# board.net
KiCad netlist of a schematic drawn in EAGLE
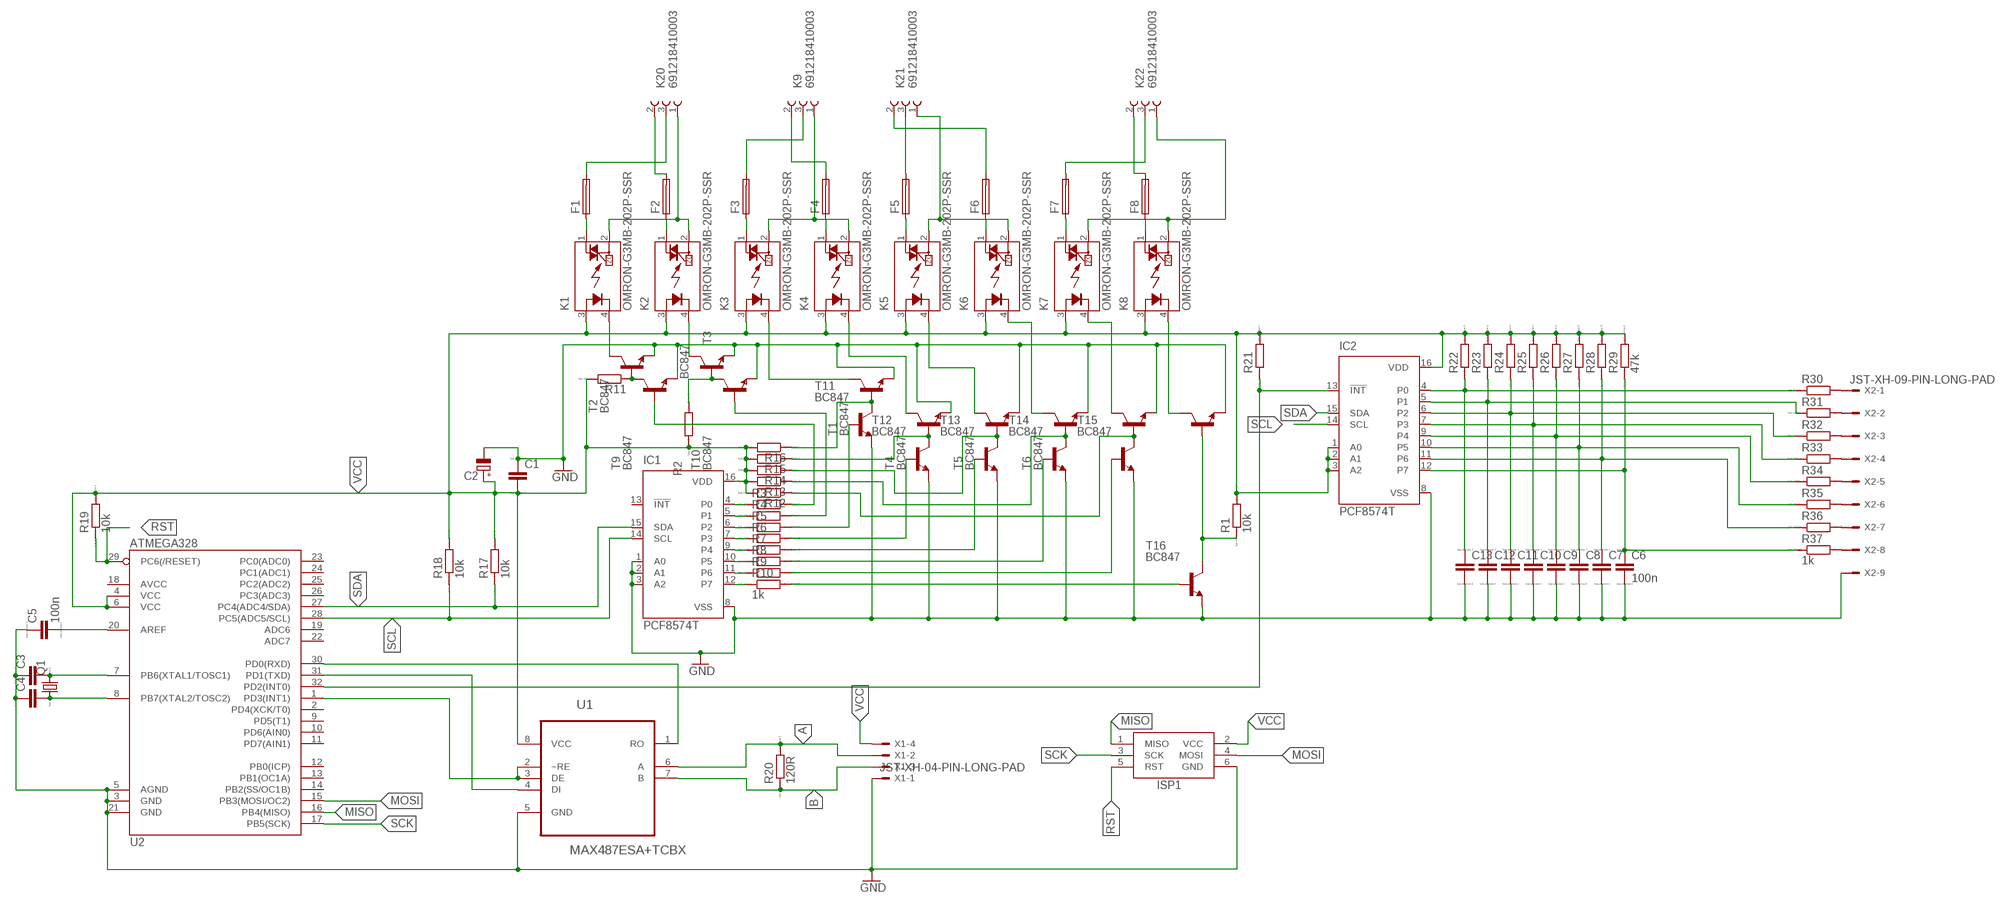
[diagram p0: schematic, sheet 1]

(export (version "E")
  (design (tool "Eeschema 10.0.6"))
  (components
    (comp (ref "C1")
      (value "CC1206")
      (footprint "eagle-import:C1206")
      (libsource (lib "eagle-import") (part "CC1206"))
    )
    (comp (ref "C2")
      (value "CPOL-EU150CLZ-0810")
      (footprint "eagle-import:150CLZ-0810")
      (libsource (lib "eagle-import") (part "CPOL-EU150CLZ-0810"))
    )
    (comp (ref "C3") (value "C") (footprint "eagle-import:C0805") (libsource (lib "eagle-import") (part "C")))
    (comp (ref "C4") (value "C") (footprint "eagle-import:C0805") (libsource (lib "eagle-import") (part "C")))
    (comp (ref "C5")
      (value "100n")
      (footprint "eagle-import:C0805")
      (libsource (lib "eagle-import") (part "C"))
    )
    (comp (ref "C6")
      (value "100n")
      (footprint "eagle-import:C0805")
      (libsource (lib "eagle-import") (part "C"))
    )
    (comp (ref "C7") (value "C") (footprint "eagle-import:C0805") (libsource (lib "eagle-import") (part "C")))
    (comp (ref "C8") (value "C") (footprint "eagle-import:C0805") (libsource (lib "eagle-import") (part "C")))
    (comp (ref "C9") (value "C") (footprint "eagle-import:C0805") (libsource (lib "eagle-import") (part "C")))
    (comp (ref "C10")
      (value "C")
      (footprint "eagle-import:C0805")
      (libsource (lib "eagle-import") (part "C"))
    )
    (comp (ref "C11")
      (value "C")
      (footprint "eagle-import:C0805")
      (libsource (lib "eagle-import") (part "C"))
    )
    (comp (ref "C12")
      (value "C")
      (footprint "eagle-import:C0805")
      (libsource (lib "eagle-import") (part "C"))
    )
    (comp (ref "C13")
      (value "C")
      (footprint "eagle-import:C0805")
      (libsource (lib "eagle-import") (part "C"))
    )
    (comp (ref "F1")
      (value "FUSELITTLEFUSE")
      (footprint "eagle-import:LITTLEFUSE")
      (libsource (lib "eagle-import") (part "FUSELITTLEFUSE"))
    )
    (comp (ref "F2")
      (value "FUSELITTLEFUSE")
      (footprint "eagle-import:LITTLEFUSE")
      (libsource (lib "eagle-import") (part "FUSELITTLEFUSE"))
    )
    (comp (ref "F3")
      (value "FUSELITTLEFUSE")
      (footprint "eagle-import:LITTLEFUSE")
      (libsource (lib "eagle-import") (part "FUSELITTLEFUSE"))
    )
    (comp (ref "F4")
      (value "FUSELITTLEFUSE")
      (footprint "eagle-import:LITTLEFUSE")
      (libsource (lib "eagle-import") (part "FUSELITTLEFUSE"))
    )
    (comp (ref "F5")
      (value "FUSELITTLEFUSE")
      (footprint "eagle-import:LITTLEFUSE")
      (libsource (lib "eagle-import") (part "FUSELITTLEFUSE"))
    )
    (comp (ref "F6")
      (value "FUSELITTLEFUSE")
      (footprint "eagle-import:LITTLEFUSE")
      (libsource (lib "eagle-import") (part "FUSELITTLEFUSE"))
    )
    (comp (ref "F7")
      (value "FUSELITTLEFUSE")
      (footprint "eagle-import:LITTLEFUSE")
      (libsource (lib "eagle-import") (part "FUSELITTLEFUSE"))
    )
    (comp (ref "F8")
      (value "FUSELITTLEFUSE")
      (footprint "eagle-import:LITTLEFUSE")
      (libsource (lib "eagle-import") (part "FUSELITTLEFUSE"))
    )
    (comp (ref "IC1")
      (value "PCF8574T")
      (footprint "eagle-import:SO16W")
      (fields (field (name "MPN") "PCF8574T/3,512"))
      (libsource (lib "eagle-import") (part "PCF8574T"))
    )
    (comp (ref "IC2")
      (value "PCF8574T")
      (footprint "eagle-import:SO16W")
      (fields (field (name "MPN") "PCF8574T/3,512"))
      (libsource (lib "eagle-import") (part "PCF8574T"))
    )
    (comp (ref "ISP1")
      (value "AVRISP-6")
      (footprint "eagle-import:AVRISP")
      (libsource (lib "eagle-import") (part "AVRISP-6"))
    )
    (comp (ref "K1")
      (value "OMRON-G3MB-202P-SSR")
      (footprint "eagle-import:OMRON-G3MB-202P-SSR")
      (libsource (lib "eagle-import") (part "OMRON-G3MB-202P-SSR"))
    )
    (comp (ref "K2")
      (value "OMRON-G3MB-202P-SSR")
      (footprint "eagle-import:OMRON-G3MB-202P-SSR")
      (libsource (lib "eagle-import") (part "OMRON-G3MB-202P-SSR"))
    )
    (comp (ref "K3")
      (value "OMRON-G3MB-202P-SSR")
      (footprint "eagle-import:OMRON-G3MB-202P-SSR")
      (libsource (lib "eagle-import") (part "OMRON-G3MB-202P-SSR"))
    )
    (comp (ref "K4")
      (value "OMRON-G3MB-202P-SSR")
      (footprint "eagle-import:OMRON-G3MB-202P-SSR")
      (libsource (lib "eagle-import") (part "OMRON-G3MB-202P-SSR"))
    )
    (comp (ref "K5")
      (value "OMRON-G3MB-202P-SSR")
      (footprint "eagle-import:OMRON-G3MB-202P-SSR")
      (libsource (lib "eagle-import") (part "OMRON-G3MB-202P-SSR"))
    )
    (comp (ref "K6")
      (value "OMRON-G3MB-202P-SSR")
      (footprint "eagle-import:OMRON-G3MB-202P-SSR")
      (libsource (lib "eagle-import") (part "OMRON-G3MB-202P-SSR"))
    )
    (comp (ref "K7")
      (value "OMRON-G3MB-202P-SSR")
      (footprint "eagle-import:OMRON-G3MB-202P-SSR")
      (libsource (lib "eagle-import") (part "OMRON-G3MB-202P-SSR"))
    )
    (comp (ref "K8")
      (value "OMRON-G3MB-202P-SSR")
      (footprint "eagle-import:OMRON-G3MB-202P-SSR")
      (libsource (lib "eagle-import") (part "OMRON-G3MB-202P-SSR"))
    )
    (comp (ref "K9")
      (value "691218410003")
      (footprint "eagle-import:691218410003")
      (libsource (lib "eagle-import") (part "691218410003"))
    )
    (comp (ref "K20")
      (value "691218410003")
      (footprint "eagle-import:691218410003")
      (libsource (lib "eagle-import") (part "691218410003"))
    )
    (comp (ref "K21")
      (value "691218410003")
      (footprint "eagle-import:691218410003")
      (libsource (lib "eagle-import") (part "691218410003"))
    )
    (comp (ref "K22")
      (value "691218410003")
      (footprint "eagle-import:691218410003")
      (libsource (lib "eagle-import") (part "691218410003"))
    )
    (comp (ref "Q1")
      (value "CRYSTALHC49S")
      (footprint "eagle-import:HC49_S")
      (libsource (lib "eagle-import") (part "CRYSTALHC49S"))
    )
    (comp (ref "R1")
      (value "10k")
      (footprint "eagle-import:R1206")
      (libsource (lib "eagle-import") (part "RR1206"))
    )
    (comp (ref "R2")
      (value "RR1206")
      (footprint "eagle-import:R1206")
      (libsource (lib "eagle-import") (part "RR1206"))
    )
    (comp (ref "R3")
      (value "RR1206")
      (footprint "eagle-import:R1206")
      (libsource (lib "eagle-import") (part "RR1206"))
    )
    (comp (ref "R4")
      (value "RR1206")
      (footprint "eagle-import:R1206")
      (libsource (lib "eagle-import") (part "RR1206"))
    )
    (comp (ref "R5")
      (value "RR1206")
      (footprint "eagle-import:R1206")
      (libsource (lib "eagle-import") (part "RR1206"))
    )
    (comp (ref "R6")
      (value "RR1206")
      (footprint "eagle-import:R1206")
      (libsource (lib "eagle-import") (part "RR1206"))
    )
    (comp (ref "R7")
      (value "RR1206")
      (footprint "eagle-import:R1206")
      (libsource (lib "eagle-import") (part "RR1206"))
    )
    (comp (ref "R8")
      (value "RR1206")
      (footprint "eagle-import:R1206")
      (libsource (lib "eagle-import") (part "RR1206"))
    )
    (comp (ref "R9")
      (value "RR1206")
      (footprint "eagle-import:R1206")
      (libsource (lib "eagle-import") (part "RR1206"))
    )
    (comp (ref "R10")
      (value "1k")
      (footprint "eagle-import:R1206")
      (libsource (lib "eagle-import") (part "RR1206"))
    )
    (comp (ref "R11")
      (value "RR1206")
      (footprint "eagle-import:R1206")
      (libsource (lib "eagle-import") (part "RR1206"))
    )
    (comp (ref "R12")
      (value "RR1206")
      (footprint "eagle-import:R1206")
      (libsource (lib "eagle-import") (part "RR1206"))
    )
    (comp (ref "R13")
      (value "RR1206")
      (footprint "eagle-import:R1206")
      (libsource (lib "eagle-import") (part "RR1206"))
    )
    (comp (ref "R14")
      (value "RR1206")
      (footprint "eagle-import:R1206")
      (libsource (lib "eagle-import") (part "RR1206"))
    )
    (comp (ref "R15")
      (value "RR1206")
      (footprint "eagle-import:R1206")
      (libsource (lib "eagle-import") (part "RR1206"))
    )
    (comp (ref "R16")
      (value "RR1206")
      (footprint "eagle-import:R1206")
      (libsource (lib "eagle-import") (part "RR1206"))
    )
    (comp (ref "R17")
      (value "10k")
      (footprint "eagle-import:R1206")
      (libsource (lib "eagle-import") (part "RR1206"))
    )
    (comp (ref "R18")
      (value "10k")
      (footprint "eagle-import:R1206")
      (libsource (lib "eagle-import") (part "RR1206"))
    )
    (comp (ref "R19")
      (value "10k")
      (footprint "eagle-import:R1206")
      (libsource (lib "eagle-import") (part "RR1206"))
    )
    (comp (ref "R20")
      (value "120R")
      (footprint "eagle-import:R1206")
      (libsource (lib "eagle-import") (part "RR1206"))
    )
    (comp (ref "R21")
      (value "RR1206")
      (footprint "eagle-import:R1206")
      (libsource (lib "eagle-import") (part "RR1206"))
    )
    (comp (ref "R22")
      (value "RR1206")
      (footprint "eagle-import:R1206")
      (libsource (lib "eagle-import") (part "RR1206"))
    )
    (comp (ref "R23")
      (value "RR1206")
      (footprint "eagle-import:R1206")
      (libsource (lib "eagle-import") (part "RR1206"))
    )
    (comp (ref "R24")
      (value "RR1206")
      (footprint "eagle-import:R1206")
      (libsource (lib "eagle-import") (part "RR1206"))
    )
    (comp (ref "R25")
      (value "RR1206")
      (footprint "eagle-import:R1206")
      (libsource (lib "eagle-import") (part "RR1206"))
    )
    (comp (ref "R26")
      (value "RR1206")
      (footprint "eagle-import:R1206")
      (libsource (lib "eagle-import") (part "RR1206"))
    )
    (comp (ref "R27")
      (value "RR1206")
      (footprint "eagle-import:R1206")
      (libsource (lib "eagle-import") (part "RR1206"))
    )
    (comp (ref "R28")
      (value "RR1206")
      (footprint "eagle-import:R1206")
      (libsource (lib "eagle-import") (part "RR1206"))
    )
    (comp (ref "R29")
      (value "47k")
      (footprint "eagle-import:R1206")
      (libsource (lib "eagle-import") (part "RR1206"))
    )
    (comp (ref "R30")
      (value "RR1206")
      (footprint "eagle-import:R1206")
      (libsource (lib "eagle-import") (part "RR1206"))
    )
    (comp (ref "R31")
      (value "RR1206")
      (footprint "eagle-import:R1206")
      (libsource (lib "eagle-import") (part "RR1206"))
    )
    (comp (ref "R32")
      (value "RR1206")
      (footprint "eagle-import:R1206")
      (libsource (lib "eagle-import") (part "RR1206"))
    )
    (comp (ref "R33")
      (value "RR1206")
      (footprint "eagle-import:R1206")
      (libsource (lib "eagle-import") (part "RR1206"))
    )
    (comp (ref "R34")
      (value "RR1206")
      (footprint "eagle-import:R1206")
      (libsource (lib "eagle-import") (part "RR1206"))
    )
    (comp (ref "R35")
      (value "RR1206")
      (footprint "eagle-import:R1206")
      (libsource (lib "eagle-import") (part "RR1206"))
    )
    (comp (ref "R36")
      (value "RR1206")
      (footprint "eagle-import:R1206")
      (libsource (lib "eagle-import") (part "RR1206"))
    )
    (comp (ref "R37")
      (value "1k")
      (footprint "eagle-import:R1206")
      (libsource (lib "eagle-import") (part "RR1206"))
    )
    (comp (ref "T1")
      (value "BC847")
      (footprint "eagle-import:SOT23")
      (libsource (lib "eagle-import") (part "transistor_402_BC847"))
    )
    (comp (ref "T2")
      (value "BC847")
      (footprint "eagle-import:SOT23")
      (libsource (lib "eagle-import") (part "transistor_402_BC847"))
    )
    (comp (ref "T3")
      (value "BC847")
      (footprint "eagle-import:SOT23")
      (libsource (lib "eagle-import") (part "transistor_402_BC847"))
    )
    (comp (ref "T4")
      (value "BC847")
      (footprint "eagle-import:SOT23")
      (libsource (lib "eagle-import") (part "transistor_402_BC847"))
    )
    (comp (ref "T5")
      (value "BC847")
      (footprint "eagle-import:SOT23")
      (libsource (lib "eagle-import") (part "transistor_402_BC847"))
    )
    (comp (ref "T6")
      (value "BC847")
      (footprint "eagle-import:SOT23")
      (libsource (lib "eagle-import") (part "transistor_402_BC847"))
    )
    (comp (ref "T7")
      (value "BC847")
      (footprint "eagle-import:SOT23")
      (libsource (lib "eagle-import") (part "transistor_402_BC847"))
    )
    (comp (ref "T8")
      (value "BC847")
      (footprint "eagle-import:SOT23")
      (libsource (lib "eagle-import") (part "transistor_402_BC847"))
    )
    (comp (ref "T9")
      (value "BC847")
      (footprint "eagle-import:SOT23")
      (libsource (lib "eagle-import") (part "BC847"))
    )
    (comp (ref "T10")
      (value "BC847")
      (footprint "eagle-import:SOT23")
      (libsource (lib "eagle-import") (part "BC847"))
    )
    (comp (ref "T11")
      (value "BC847")
      (footprint "eagle-import:SOT23")
      (libsource (lib "eagle-import") (part "BC847"))
    )
    (comp (ref "T12")
      (value "BC847")
      (footprint "eagle-import:SOT23")
      (libsource (lib "eagle-import") (part "BC847"))
    )
    (comp (ref "T13")
      (value "BC847")
      (footprint "eagle-import:SOT23")
      (libsource (lib "eagle-import") (part "BC847"))
    )
    (comp (ref "T14")
      (value "BC847")
      (footprint "eagle-import:SOT23")
      (libsource (lib "eagle-import") (part "BC847"))
    )
    (comp (ref "T15")
      (value "BC847")
      (footprint "eagle-import:SOT23")
      (libsource (lib "eagle-import") (part "BC847"))
    )
    (comp (ref "T16")
      (value "BC847")
      (footprint "eagle-import:SOT23")
      (libsource (lib "eagle-import") (part "BC847"))
    )
    (comp (ref "U1")
      (value "MAX487ESA+TCBX")
      (footprint "eagle-import:SOIC127P600X175-8N")
      (fields (field (name "MF") "Maxim Integrated"))
      (libsource (lib "eagle-import") (part "MAX487ESA+TCBX"))
    )
    (comp (ref "U2")
      (value "ATMEGA328")
      (footprint "eagle-import:TQFP32-08")
      (libsource (lib "eagle-import") (part "ATMEGA328"))
    )
    (comp (ref "X1")
      (value "JST-XH-04-PIN-LONG-PAD")
      (footprint "eagle-import:JST-XH-04-PACKAGE-LONG-PAD")
      (libsource (lib "eagle-import") (part "JST-XH-04-PIN-LONG-PAD"))
    )
    (comp (ref "X2")
      (value "JST-XH-09-PIN-LONG-PAD")
      (footprint "eagle-import:JST-XH-09-PACKAGE-LONG-PAD")
      (libsource (lib "eagle-import") (part "JST-XH-09-PIN-LONG-PAD"))
    )
  )
  (nets
    (net (code "1") (name "A") (class "Default")
      (node (ref "R20") (pin "2") (pinfunction "2_2") (pintype "passive"))
      (node (ref "U1") (pin "6") (pinfunction "A_6") (pintype "bidirectional"))
      (node (ref "X1") (pin "2") (pinfunction "S_2") (pintype "passive"))
    )
    (net (code "2") (name "B") (class "Default")
      (node (ref "R20") (pin "1") (pinfunction "1_1") (pintype "passive"))
      (node (ref "U1") (pin "7") (pinfunction "B_7") (pintype "bidirectional"))
      (node (ref "X1") (pin "3") (pinfunction "S_3") (pintype "passive"))
    )
    (net (code "3") (name "GND") (class "Default")
      (node (ref "C1") (pin "1") (pinfunction "1_1") (pintype "passive"))
      (node (ref "C10") (pin "2") (pinfunction "2_2") (pintype "passive"))
      (node (ref "C11") (pin "2") (pinfunction "2_2") (pintype "passive"))
      (node (ref "C12") (pin "2") (pinfunction "2_2") (pintype "passive"))
      (node (ref "C13") (pin "2") (pinfunction "2_2") (pintype "passive"))
      (node (ref "C2") (pin "-") (pinfunction "-_-") (pintype "passive"))
      (node (ref "C3") (pin "1") (pinfunction "1_1") (pintype "passive"))
      (node (ref "C4") (pin "1") (pinfunction "1_1") (pintype "passive"))
      (node (ref "C5") (pin "1") (pinfunction "1_1") (pintype "passive"))
      (node (ref "C6") (pin "2") (pinfunction "2_2") (pintype "passive"))
      (node (ref "C7") (pin "2") (pinfunction "2_2") (pintype "passive"))
      (node (ref "C8") (pin "2") (pinfunction "2_2") (pintype "passive"))
      (node (ref "C9") (pin "2") (pinfunction "2_2") (pintype "passive"))
      (node (ref "IC1") (pin "1") (pinfunction "A0_1") (pintype "input"))
      (node (ref "IC1") (pin "2") (pinfunction "A1_2") (pintype "input"))
      (node (ref "IC1") (pin "3") (pinfunction "A2_3") (pintype "input"))
      (node (ref "IC1") (pin "8") (pinfunction "VSS_8") (pintype "power_in"))
      (node (ref "IC2") (pin "8") (pinfunction "VSS_8") (pintype "power_in"))
      (node (ref "ISP1") (pin "6") (pinfunction "GND_6") (pintype "power_in"))
      (node (ref "T1") (pin "2") (pinfunction "E_2") (pintype "passive"))
      (node (ref "T10") (pin "2") (pinfunction "E_2") (pintype "passive"))
      (node (ref "T11") (pin "2") (pinfunction "E_2") (pintype "passive"))
      (node (ref "T12") (pin "2") (pinfunction "E_2") (pintype "passive"))
      (node (ref "T13") (pin "2") (pinfunction "E_2") (pintype "passive"))
      (node (ref "T14") (pin "2") (pinfunction "E_2") (pintype "passive"))
      (node (ref "T15") (pin "2") (pinfunction "E_2") (pintype "passive"))
      (node (ref "T16") (pin "2") (pinfunction "E_2") (pintype "passive"))
      (node (ref "T2") (pin "2") (pinfunction "E_2") (pintype "passive"))
      (node (ref "T3") (pin "2") (pinfunction "E_2") (pintype "passive"))
      (node (ref "T4") (pin "2") (pinfunction "E_2") (pintype "passive"))
      (node (ref "T5") (pin "2") (pinfunction "E_2") (pintype "passive"))
      (node (ref "T6") (pin "2") (pinfunction "E_2") (pintype "passive"))
      (node (ref "T7") (pin "2") (pinfunction "E_2") (pintype "passive"))
      (node (ref "T8") (pin "2") (pinfunction "E_2") (pintype "passive"))
      (node (ref "T9") (pin "2") (pinfunction "E_2") (pintype "passive"))
      (node (ref "U1") (pin "5") (pinfunction "GND_5") (pintype "passive"))
      (node (ref "U2") (pin "21") (pinfunction "GND_21") (pintype "bidirectional"))
      (node (ref "U2") (pin "3") (pinfunction "GND_3") (pintype "bidirectional"))
      (node (ref "U2") (pin "5") (pinfunction "AGND_5") (pintype "bidirectional"))
      (node (ref "X1") (pin "1") (pinfunction "S_1") (pintype "passive"))
      (node (ref "X2") (pin "9") (pinfunction "S_9") (pintype "passive"))
    )
    (net (code "4") (name "MISO") (class "Default")
      (node (ref "ISP1") (pin "1") (pinfunction "MISO_1") (pintype "input"))
      (node (ref "U2") (pin "16") (pinfunction "PB4(MISO)_16") (pintype "bidirectional"))
    )
    (net (code "5") (name "MOSI") (class "Default")
      (node (ref "ISP1") (pin "4") (pinfunction "MOSI_4") (pintype "output"))
      (node (ref "U2") (pin "15") (pinfunction "PB3(MOSI/OC2)_15") (pintype "bidirectional"))
    )
    (net (code "6") (name "Net-(IC1-P0)") (class "Default")
      (node (ref "IC1") (pin "4") (pinfunction "P0_4") (pintype "bidirectional"))
      (node (ref "R3") (pin "1") (pinfunction "1_1") (pintype "passive"))
    )
    (net (code "7") (name "Net-(IC1-P1)") (class "Default")
      (node (ref "IC1") (pin "5") (pinfunction "P1_5") (pintype "bidirectional"))
      (node (ref "R4") (pin "1") (pinfunction "1_1") (pintype "passive"))
    )
    (net (code "8") (name "Net-(IC1-P2)") (class "Default")
      (node (ref "IC1") (pin "6") (pinfunction "P2_6") (pintype "bidirectional"))
      (node (ref "R5") (pin "1") (pinfunction "1_1") (pintype "passive"))
    )
    (net (code "9") (name "Net-(IC1-P3)") (class "Default")
      (node (ref "IC1") (pin "7") (pinfunction "P3_7") (pintype "bidirectional"))
      (node (ref "R6") (pin "1") (pinfunction "1_1") (pintype "passive"))
    )
    (net (code "10") (name "Net-(IC1-P4)") (class "Default")
      (node (ref "IC1") (pin "9") (pinfunction "P4_9") (pintype "bidirectional"))
      (node (ref "R7") (pin "1") (pinfunction "1_1") (pintype "passive"))
    )
    (net (code "11") (name "Net-(IC1-P5)") (class "Default")
      (node (ref "IC1") (pin "10") (pinfunction "P5_10") (pintype "bidirectional"))
      (node (ref "R8") (pin "1") (pinfunction "1_1") (pintype "passive"))
    )
    (net (code "12") (name "Net-(IC1-P6)") (class "Default")
      (node (ref "IC1") (pin "11") (pinfunction "P6_11") (pintype "bidirectional"))
      (node (ref "R9") (pin "1") (pinfunction "1_1") (pintype "passive"))
    )
    (net (code "13") (name "Net-(IC1-P7)") (class "Default")
      (node (ref "IC1") (pin "12") (pinfunction "P7_12") (pintype "bidirectional"))
      (node (ref "R10") (pin "1") (pinfunction "1_1") (pintype "passive"))
    )
    (net (code "14") (name "Net-(IC2-P0)") (class "Default")
      (node (ref "C13") (pin "1") (pinfunction "1_1") (pintype "passive"))
      (node (ref "IC2") (pin "4") (pinfunction "P0_4") (pintype "bidirectional"))
      (node (ref "R22") (pin "1") (pinfunction "1_1") (pintype "passive"))
      (node (ref "R30") (pin "1") (pinfunction "1_1") (pintype "passive"))
    )
    (net (code "15") (name "Net-(IC2-P1)") (class "Default")
      (node (ref "C12") (pin "1") (pinfunction "1_1") (pintype "passive"))
      (node (ref "IC2") (pin "5") (pinfunction "P1_5") (pintype "bidirectional"))
      (node (ref "R23") (pin "1") (pinfunction "1_1") (pintype "passive"))
      (node (ref "R31") (pin "1") (pinfunction "1_1") (pintype "passive"))
    )
    (net (code "16") (name "Net-(IC2-P2)") (class "Default")
      (node (ref "C11") (pin "1") (pinfunction "1_1") (pintype "passive"))
      (node (ref "IC2") (pin "6") (pinfunction "P2_6") (pintype "bidirectional"))
      (node (ref "R24") (pin "1") (pinfunction "1_1") (pintype "passive"))
      (node (ref "R32") (pin "1") (pinfunction "1_1") (pintype "passive"))
    )
    (net (code "17") (name "Net-(IC2-P3)") (class "Default")
      (node (ref "C10") (pin "1") (pinfunction "1_1") (pintype "passive"))
      (node (ref "IC2") (pin "7") (pinfunction "P3_7") (pintype "bidirectional"))
      (node (ref "R25") (pin "1") (pinfunction "1_1") (pintype "passive"))
      (node (ref "R33") (pin "1") (pinfunction "1_1") (pintype "passive"))
    )
    (net (code "18") (name "Net-(IC2-P4)") (class "Default")
      (node (ref "C9") (pin "1") (pinfunction "1_1") (pintype "passive"))
      (node (ref "IC2") (pin "9") (pinfunction "P4_9") (pintype "bidirectional"))
      (node (ref "R26") (pin "1") (pinfunction "1_1") (pintype "passive"))
      (node (ref "R34") (pin "1") (pinfunction "1_1") (pintype "passive"))
    )
    (net (code "19") (name "Net-(IC2-P5)") (class "Default")
      (node (ref "C8") (pin "1") (pinfunction "1_1") (pintype "passive"))
      (node (ref "IC2") (pin "10") (pinfunction "P5_10") (pintype "bidirectional"))
      (node (ref "R27") (pin "1") (pinfunction "1_1") (pintype "passive"))
      (node (ref "R35") (pin "1") (pinfunction "1_1") (pintype "passive"))
    )
    (net (code "20") (name "Net-(IC2-P6)") (class "Default")
      (node (ref "C7") (pin "1") (pinfunction "1_1") (pintype "passive"))
      (node (ref "IC2") (pin "11") (pinfunction "P6_11") (pintype "bidirectional"))
      (node (ref "R28") (pin "1") (pinfunction "1_1") (pintype "passive"))
      (node (ref "R36") (pin "1") (pinfunction "1_1") (pintype "passive"))
    )
    (net (code "21") (name "Net-(IC2-P7)") (class "Default")
      (node (ref "C6") (pin "1") (pinfunction "1_1") (pintype "passive"))
      (node (ref "IC2") (pin "12") (pinfunction "P7_12") (pintype "bidirectional"))
      (node (ref "R29") (pin "1") (pinfunction "1_1") (pintype "passive"))
      (node (ref "R37") (pin "1") (pinfunction "1_1") (pintype "passive"))
    )
    (net (code "22") (name "Net-(IC2-~{INT})") (class "Default")
      (node (ref "IC2") (pin "13") (pinfunction "~{INT}_13") (pintype "output"))
      (node (ref "R21") (pin "1") (pinfunction "1_1") (pintype "passive"))
      (node (ref "U2") (pin "32") (pinfunction "PD2(INT0)_32") (pintype "bidirectional"))
    )
    (net (code "23") (name "Net-(K1-DS1)") (class "Default")
      (node (ref "F1") (pin "1") (pinfunction "1_1") (pintype "passive"))
      (node (ref "K1") (pin "1") (pinfunction "DS1_1") (pintype "passive"))
    )
    (net (code "24") (name "Net-(K1-DS2)") (class "Default")
      (node (ref "K1") (pin "2") (pinfunction "DS2_2") (pintype "passive"))
      (node (ref "K2") (pin "2") (pinfunction "DS2_2") (pintype "passive"))
      (node (ref "K20") (pin "1") (pinfunction "3_1") (pintype "passive"))
    )
    (net (code "25") (name "Net-(K1-K)") (class "Default")
      (node (ref "K1") (pin "4") (pinfunction "K_4") (pintype "passive"))
      (node (ref "T2") (pin "3") (pinfunction "C_3") (pintype "passive"))
    )
    (net (code "26") (name "Net-(K2-DS1)") (class "Default")
      (node (ref "F2") (pin "1") (pinfunction "1_1") (pintype "passive"))
      (node (ref "K2") (pin "1") (pinfunction "DS1_1") (pintype "passive"))
    )
    (net (code "27") (name "Net-(K2-K)") (class "Default")
      (node (ref "K2") (pin "4") (pinfunction "K_4") (pintype "passive"))
      (node (ref "T3") (pin "3") (pinfunction "C_3") (pintype "passive"))
    )
    (net (code "28") (name "Net-(K3-DS1)") (class "Default")
      (node (ref "F3") (pin "1") (pinfunction "1_1") (pintype "passive"))
      (node (ref "K3") (pin "1") (pinfunction "DS1_1") (pintype "passive"))
    )
    (net (code "29") (name "Net-(K3-DS2)") (class "Default")
      (node (ref "K3") (pin "2") (pinfunction "DS2_2") (pintype "passive"))
      (node (ref "K4") (pin "2") (pinfunction "DS2_2") (pintype "passive"))
      (node (ref "K9") (pin "1") (pinfunction "3_1") (pintype "passive"))
    )
    (net (code "30") (name "Net-(K3-K)") (class "Default")
      (node (ref "K3") (pin "4") (pinfunction "K_4") (pintype "passive"))
      (node (ref "T1") (pin "3") (pinfunction "C_3") (pintype "passive"))
    )
    (net (code "31") (name "Net-(K4-DS1)") (class "Default")
      (node (ref "F4") (pin "1") (pinfunction "1_1") (pintype "passive"))
      (node (ref "K4") (pin "1") (pinfunction "DS1_1") (pintype "passive"))
    )
    (net (code "32") (name "Net-(K4-K)") (class "Default")
      (node (ref "K4") (pin "4") (pinfunction "K_4") (pintype "passive"))
      (node (ref "T4") (pin "3") (pinfunction "C_3") (pintype "passive"))
    )
    (net (code "33") (name "Net-(K5-DS1)") (class "Default")
      (node (ref "F5") (pin "1") (pinfunction "1_1") (pintype "passive"))
      (node (ref "K5") (pin "1") (pinfunction "DS1_1") (pintype "passive"))
    )
    (net (code "34") (name "Net-(K5-K)") (class "Default")
      (node (ref "K5") (pin "4") (pinfunction "K_4") (pintype "passive"))
      (node (ref "T5") (pin "3") (pinfunction "C_3") (pintype "passive"))
    )
    (net (code "35") (name "Net-(K6-DS1)") (class "Default")
      (node (ref "F6") (pin "1") (pinfunction "1_1") (pintype "passive"))
      (node (ref "K6") (pin "1") (pinfunction "DS1_1") (pintype "passive"))
    )
    (net (code "36") (name "Net-(K6-K)") (class "Default")
      (node (ref "K6") (pin "4") (pinfunction "K_4") (pintype "passive"))
      (node (ref "T6") (pin "3") (pinfunction "C_3") (pintype "passive"))
    )
    (net (code "37") (name "Net-(K7-DS1)") (class "Default")
      (node (ref "F7") (pin "1") (pinfunction "1_1") (pintype "passive"))
      (node (ref "K7") (pin "1") (pinfunction "DS1_1") (pintype "passive"))
    )
    (net (code "38") (name "Net-(K7-K)") (class "Default")
      (node (ref "K7") (pin "4") (pinfunction "K_4") (pintype "passive"))
      (node (ref "T7") (pin "3") (pinfunction "C_3") (pintype "passive"))
    )
    (net (code "39") (name "Net-(K8-DS1)") (class "Default")
      (node (ref "F8") (pin "1") (pinfunction "1_1") (pintype "passive"))
      (node (ref "K8") (pin "1") (pinfunction "DS1_1") (pintype "passive"))
    )
    (net (code "40") (name "Net-(K8-K)") (class "Default")
      (node (ref "K8") (pin "4") (pinfunction "K_4") (pintype "passive"))
      (node (ref "T8") (pin "3") (pinfunction "C_3") (pintype "passive"))
    )
    (net (code "41") (name "Net-(K9-1)") (class "Default")
      (node (ref "F4") (pin "2") (pinfunction "2_2") (pintype "passive"))
      (node (ref "K9") (pin "2") (pinfunction "1_2") (pintype "passive"))
    )
    (net (code "42") (name "Net-(K9-2)") (class "Default")
      (node (ref "F3") (pin "2") (pinfunction "2_2") (pintype "passive"))
      (node (ref "K9") (pin "3") (pinfunction "2_3") (pintype "passive"))
    )
    (net (code "43") (name "Net-(K20-1)") (class "Default")
      (node (ref "F2") (pin "2") (pinfunction "2_2") (pintype "passive"))
      (node (ref "K20") (pin "2") (pinfunction "1_2") (pintype "passive"))
    )
    (net (code "44") (name "Net-(K20-2)") (class "Default")
      (node (ref "F1") (pin "2") (pinfunction "2_2") (pintype "passive"))
      (node (ref "K20") (pin "3") (pinfunction "2_3") (pintype "passive"))
    )
    (net (code "45") (name "Net-(K21-1)") (class "Default")
      (node (ref "F6") (pin "2") (pinfunction "2_2") (pintype "passive"))
      (node (ref "K21") (pin "2") (pinfunction "1_2") (pintype "passive"))
    )
    (net (code "46") (name "Net-(K21-2)") (class "Default")
      (node (ref "F5") (pin "2") (pinfunction "2_2") (pintype "passive"))
      (node (ref "K21") (pin "3") (pinfunction "2_3") (pintype "passive"))
    )
    (net (code "47") (name "Net-(K21-3)") (class "Default")
      (node (ref "K21") (pin "1") (pinfunction "3_1") (pintype "passive"))
      (node (ref "K5") (pin "2") (pinfunction "DS2_2") (pintype "passive"))
      (node (ref "K6") (pin "2") (pinfunction "DS2_2") (pintype "passive"))
    )
    (net (code "48") (name "Net-(K22-1)") (class "Default")
      (node (ref "F8") (pin "2") (pinfunction "2_2") (pintype "passive"))
      (node (ref "K22") (pin "2") (pinfunction "1_2") (pintype "passive"))
    )
    (net (code "49") (name "Net-(K22-2)") (class "Default")
      (node (ref "F7") (pin "2") (pinfunction "2_2") (pintype "passive"))
      (node (ref "K22") (pin "3") (pinfunction "2_3") (pintype "passive"))
    )
    (net (code "50") (name "Net-(K22-3)") (class "Default")
      (node (ref "K22") (pin "1") (pinfunction "3_1") (pintype "passive"))
      (node (ref "K7") (pin "2") (pinfunction "DS2_2") (pintype "passive"))
      (node (ref "K8") (pin "2") (pinfunction "DS2_2") (pintype "passive"))
    )
    (net (code "51") (name "Net-(T1-B)") (class "Default")
      (node (ref "R16") (pin "1") (pinfunction "1_1") (pintype "passive"))
      (node (ref "T1") (pin "1") (pinfunction "B_1") (pintype "passive"))
      (node (ref "T11") (pin "3") (pinfunction "C_3") (pintype "passive"))
    )
    (net (code "52") (name "Net-(T2-B)") (class "Default")
      (node (ref "R11") (pin "1") (pinfunction "1_1") (pintype "passive"))
      (node (ref "T2") (pin "1") (pinfunction "B_1") (pintype "passive"))
      (node (ref "T9") (pin "3") (pinfunction "C_3") (pintype "passive"))
    )
    (net (code "53") (name "Net-(T9-B)") (class "Default")
      (node (ref "R3") (pin "2") (pinfunction "2_2") (pintype "passive"))
      (node (ref "T9") (pin "1") (pinfunction "B_1") (pintype "passive"))
    )
    (net (code "54") (name "Net-(T10-B)") (class "Default")
      (node (ref "R4") (pin "2") (pinfunction "2_2") (pintype "passive"))
      (node (ref "T10") (pin "1") (pinfunction "B_1") (pintype "passive"))
    )
    (net (code "55") (name "Net-(T10-C)") (class "Default")
      (node (ref "R2") (pin "2") (pinfunction "2_2") (pintype "passive"))
      (node (ref "T10") (pin "3") (pinfunction "C_3") (pintype "passive"))
      (node (ref "T3") (pin "1") (pinfunction "B_1") (pintype "passive"))
    )
    (net (code "56") (name "Net-(T11-B)") (class "Default")
      (node (ref "R5") (pin "2") (pinfunction "2_2") (pintype "passive"))
      (node (ref "T11") (pin "1") (pinfunction "B_1") (pintype "passive"))
    )
    (net (code "57") (name "Net-(T12-B)") (class "Default")
      (node (ref "R6") (pin "2") (pinfunction "2_2") (pintype "passive"))
      (node (ref "T12") (pin "1") (pinfunction "B_1") (pintype "passive"))
    )
    (net (code "58") (name "Net-(T12-C)") (class "Default")
      (node (ref "R15") (pin "1") (pinfunction "1_1") (pintype "passive"))
      (node (ref "T12") (pin "3") (pinfunction "C_3") (pintype "passive"))
      (node (ref "T4") (pin "1") (pinfunction "B_1") (pintype "passive"))
    )
    (net (code "59") (name "Net-(T13-B)") (class "Default")
      (node (ref "R7") (pin "2") (pinfunction "2_2") (pintype "passive"))
      (node (ref "T13") (pin "1") (pinfunction "B_1") (pintype "passive"))
    )
    (net (code "60") (name "Net-(T13-C)") (class "Default")
      (node (ref "R14") (pin "1") (pinfunction "1_1") (pintype "passive"))
      (node (ref "T13") (pin "3") (pinfunction "C_3") (pintype "passive"))
      (node (ref "T5") (pin "1") (pinfunction "B_1") (pintype "passive"))
    )
    (net (code "61") (name "Net-(T14-B)") (class "Default")
      (node (ref "R8") (pin "2") (pinfunction "2_2") (pintype "passive"))
      (node (ref "T14") (pin "1") (pinfunction "B_1") (pintype "passive"))
    )
    (net (code "62") (name "Net-(T14-C)") (class "Default")
      (node (ref "R13") (pin "1") (pinfunction "1_1") (pintype "passive"))
      (node (ref "T14") (pin "3") (pinfunction "C_3") (pintype "passive"))
      (node (ref "T6") (pin "1") (pinfunction "B_1") (pintype "passive"))
    )
    (net (code "63") (name "Net-(T15-B)") (class "Default")
      (node (ref "R9") (pin "2") (pinfunction "2_2") (pintype "passive"))
      (node (ref "T15") (pin "1") (pinfunction "B_1") (pintype "passive"))
    )
    (net (code "64") (name "Net-(T15-C)") (class "Default")
      (node (ref "R12") (pin "1") (pinfunction "1_1") (pintype "passive"))
      (node (ref "T15") (pin "3") (pinfunction "C_3") (pintype "passive"))
      (node (ref "T7") (pin "1") (pinfunction "B_1") (pintype "passive"))
    )
    (net (code "65") (name "Net-(T16-B)") (class "Default")
      (node (ref "R10") (pin "2") (pinfunction "2_2") (pintype "passive"))
      (node (ref "T16") (pin "1") (pinfunction "B_1") (pintype "passive"))
    )
    (net (code "66") (name "Net-(T16-C)") (class "Default")
      (node (ref "R1") (pin "1") (pinfunction "1_1") (pintype "passive"))
      (node (ref "T16") (pin "3") (pinfunction "C_3") (pintype "passive"))
      (node (ref "T8") (pin "1") (pinfunction "B_1") (pintype "passive"))
    )
    (net (code "67") (name "Net-(U1-DE)") (class "Default")
      (node (ref "U1") (pin "2") (pinfunction "~{RE}_2") (pintype "input"))
      (node (ref "U1") (pin "3") (pinfunction "DE_3") (pintype "input"))
      (node (ref "U2") (pin "1") (pinfunction "PD3(INT1)_1") (pintype "bidirectional"))
    )
    (net (code "68") (name "Net-(U1-DI)") (class "Default")
      (node (ref "U1") (pin "4") (pinfunction "DI_4") (pintype "input"))
      (node (ref "U2") (pin "31") (pinfunction "PD1(TXD)_31") (pintype "bidirectional"))
    )
    (net (code "69") (name "Net-(U1-RO)") (class "Default")
      (node (ref "U1") (pin "1") (pinfunction "RO_1") (pintype "output"))
      (node (ref "U2") (pin "30") (pinfunction "PD0(RXD)_30") (pintype "bidirectional"))
    )
    (net (code "70") (name "Net-(U2-AREF)") (class "Default")
      (node (ref "C5") (pin "2") (pinfunction "2_2") (pintype "passive"))
      (node (ref "U2") (pin "20") (pinfunction "AREF_20") (pintype "bidirectional"))
    )
    (net (code "71") (name "Net-(U2-PB6(XTAL1{slash}TOSC1))") (class "Default")
      (node (ref "C3") (pin "2") (pinfunction "2_2") (pintype "passive"))
      (node (ref "Q1") (pin "2") (pinfunction "2_2") (pintype "passive"))
      (node (ref "U2") (pin "7") (pinfunction "PB6(XTAL1/TOSC1)_7") (pintype "bidirectional"))
    )
    (net (code "72") (name "Net-(U2-PB7(XTAL2{slash}TOSC2))") (class "Default")
      (node (ref "C4") (pin "2") (pinfunction "2_2") (pintype "passive"))
      (node (ref "Q1") (pin "1") (pinfunction "1_1") (pintype "passive"))
      (node (ref "U2") (pin "8") (pinfunction "PB7(XTAL2/TOSC2)_8") (pintype "bidirectional"))
    )
    (net (code "73") (name "Net-(X2A-S)") (class "Default")
      (node (ref "R30") (pin "2") (pinfunction "2_2") (pintype "passive"))
      (node (ref "X2") (pin "1") (pinfunction "S_1") (pintype "passive"))
    )
    (net (code "74") (name "Net-(X2B-S)") (class "Default")
      (node (ref "R31") (pin "2") (pinfunction "2_2") (pintype "passive"))
      (node (ref "X2") (pin "2") (pinfunction "S_2") (pintype "passive"))
    )
    (net (code "75") (name "Net-(X2C-S)") (class "Default")
      (node (ref "R32") (pin "2") (pinfunction "2_2") (pintype "passive"))
      (node (ref "X2") (pin "3") (pinfunction "S_3") (pintype "passive"))
    )
    (net (code "76") (name "Net-(X2D-S)") (class "Default")
      (node (ref "R33") (pin "2") (pinfunction "2_2") (pintype "passive"))
      (node (ref "X2") (pin "4") (pinfunction "S_4") (pintype "passive"))
    )
    (net (code "77") (name "Net-(X2E-S)") (class "Default")
      (node (ref "R34") (pin "2") (pinfunction "2_2") (pintype "passive"))
      (node (ref "X2") (pin "5") (pinfunction "S_5") (pintype "passive"))
    )
    (net (code "78") (name "Net-(X2F-S)") (class "Default")
      (node (ref "R35") (pin "2") (pinfunction "2_2") (pintype "passive"))
      (node (ref "X2") (pin "6") (pinfunction "S_6") (pintype "passive"))
    )
    (net (code "79") (name "Net-(X2G-S)") (class "Default")
      (node (ref "R36") (pin "2") (pinfunction "2_2") (pintype "passive"))
      (node (ref "X2") (pin "7") (pinfunction "S_7") (pintype "passive"))
    )
    (net (code "80") (name "Net-(X2H-S)") (class "Default")
      (node (ref "R37") (pin "2") (pinfunction "2_2") (pintype "passive"))
      (node (ref "X2") (pin "8") (pinfunction "S_8") (pintype "passive"))
    )
    (net (code "81") (name "RST") (class "Default")
      (node (ref "ISP1") (pin "5") (pinfunction "RST_5") (pintype "output"))
      (node (ref "R19") (pin "1") (pinfunction "1_1") (pintype "passive"))
      (node (ref "U2") (pin "29") (pinfunction "PC6(/RESET)_29") (pintype "bidirectional"))
    )
    (net (code "82") (name "SCK") (class "Default")
      (node (ref "ISP1") (pin "3") (pinfunction "SCK_3") (pintype "output"))
      (node (ref "U2") (pin "17") (pinfunction "PB5(SCK)_17") (pintype "bidirectional"))
    )
    (net (code "83") (name "SCL") (class "Default")
      (node (ref "IC1") (pin "14") (pinfunction "SCL_14") (pintype "input"))
      (node (ref "IC2") (pin "14") (pinfunction "SCL_14") (pintype "input"))
      (node (ref "R18") (pin "1") (pinfunction "1_1") (pintype "passive"))
      (node (ref "U2") (pin "28") (pinfunction "PC5(ADC5/SCL)_28") (pintype "bidirectional"))
    )
    (net (code "84") (name "SDA") (class "Default")
      (node (ref "IC1") (pin "15") (pinfunction "SDA_15") (pintype "bidirectional"))
      (node (ref "IC2") (pin "15") (pinfunction "SDA_15") (pintype "bidirectional"))
      (node (ref "R17") (pin "1") (pinfunction "1_1") (pintype "passive"))
      (node (ref "U2") (pin "27") (pinfunction "PC4(ADC4/SDA)_27") (pintype "bidirectional"))
    )
    (net (code "85") (name "VCC") (class "Default")
      (node (ref "C1") (pin "2") (pinfunction "2_2") (pintype "passive"))
      (node (ref "C2") (pin "+") (pinfunction "+_+") (pintype "passive"))
      (node (ref "IC1") (pin "16") (pinfunction "VDD_16") (pintype "power_in"))
      (node (ref "IC2") (pin "1") (pinfunction "A0_1") (pintype "input"))
      (node (ref "IC2") (pin "16") (pinfunction "VDD_16") (pintype "power_in"))
      (node (ref "IC2") (pin "2") (pinfunction "A1_2") (pintype "input"))
      (node (ref "IC2") (pin "3") (pinfunction "A2_3") (pintype "input"))
      (node (ref "ISP1") (pin "2") (pinfunction "VCC_2") (pintype "power_in"))
      (node (ref "K1") (pin "3") (pinfunction "A_3") (pintype "passive"))
      (node (ref "K2") (pin "3") (pinfunction "A_3") (pintype "passive"))
      (node (ref "K3") (pin "3") (pinfunction "A_3") (pintype "passive"))
      (node (ref "K4") (pin "3") (pinfunction "A_3") (pintype "passive"))
      (node (ref "K5") (pin "3") (pinfunction "A_3") (pintype "passive"))
      (node (ref "K6") (pin "3") (pinfunction "A_3") (pintype "passive"))
      (node (ref "K7") (pin "3") (pinfunction "A_3") (pintype "passive"))
      (node (ref "K8") (pin "3") (pinfunction "A_3") (pintype "passive"))
      (node (ref "R1") (pin "2") (pinfunction "2_2") (pintype "passive"))
      (node (ref "R11") (pin "2") (pinfunction "2_2") (pintype "passive"))
      (node (ref "R12") (pin "2") (pinfunction "2_2") (pintype "passive"))
      (node (ref "R13") (pin "2") (pinfunction "2_2") (pintype "passive"))
      (node (ref "R14") (pin "2") (pinfunction "2_2") (pintype "passive"))
      (node (ref "R15") (pin "2") (pinfunction "2_2") (pintype "passive"))
      (node (ref "R16") (pin "2") (pinfunction "2_2") (pintype "passive"))
      (node (ref "R17") (pin "2") (pinfunction "2_2") (pintype "passive"))
      (node (ref "R18") (pin "2") (pinfunction "2_2") (pintype "passive"))
      (node (ref "R19") (pin "2") (pinfunction "2_2") (pintype "passive"))
      (node (ref "R2") (pin "1") (pinfunction "1_1") (pintype "passive"))
      (node (ref "R21") (pin "2") (pinfunction "2_2") (pintype "passive"))
      (node (ref "R22") (pin "2") (pinfunction "2_2") (pintype "passive"))
      (node (ref "R23") (pin "2") (pinfunction "2_2") (pintype "passive"))
      (node (ref "R24") (pin "2") (pinfunction "2_2") (pintype "passive"))
      (node (ref "R25") (pin "2") (pinfunction "2_2") (pintype "passive"))
      (node (ref "R26") (pin "2") (pinfunction "2_2") (pintype "passive"))
      (node (ref "R27") (pin "2") (pinfunction "2_2") (pintype "passive"))
      (node (ref "R28") (pin "2") (pinfunction "2_2") (pintype "passive"))
      (node (ref "R29") (pin "2") (pinfunction "2_2") (pintype "passive"))
      (node (ref "U1") (pin "8") (pinfunction "VCC_8") (pintype "power_in"))
      (node (ref "U2") (pin "4") (pinfunction "VCC_4") (pintype "bidirectional"))
      (node (ref "U2") (pin "6") (pinfunction "VCC_6") (pintype "bidirectional"))
      (node (ref "X1") (pin "4") (pinfunction "S_4") (pintype "passive"))
    )
    (net (code "86") (name "unconnected-(IC1-~{INT}-Pad13)") (class "Default")
      (node (ref "IC1") (pin "13") (pinfunction "~{INT}_13") (pintype "output"))
    )
    (net (code "87") (name "unconnected-(U2-ADC6-Pad19)") (class "Default")
      (node (ref "U2") (pin "19") (pinfunction "ADC6_19") (pintype "bidirectional"))
    )
    (net (code "88") (name "unconnected-(U2-ADC7-Pad22)") (class "Default")
      (node (ref "U2") (pin "22") (pinfunction "ADC7_22") (pintype "bidirectional"))
    )
    (net (code "89") (name "unconnected-(U2-AVCC-Pad18)") (class "Default")
      (node (ref "U2") (pin "18") (pinfunction "AVCC_18") (pintype "bidirectional"))
    )
    (net (code "90") (name "unconnected-(U2-PB0(ICP)-Pad12)") (class "Default")
      (node (ref "U2") (pin "12") (pinfunction "PB0(ICP)_12") (pintype "bidirectional"))
    )
    (net (code "91") (name "unconnected-(U2-PB1(OC1A)-Pad13)") (class "Default")
      (node (ref "U2") (pin "13") (pinfunction "PB1(OC1A)_13") (pintype "bidirectional"))
    )
    (net (code "92") (name "unconnected-(U2-PB2(SS{slash}OC1B)-Pad14)") (class "Default")
      (node (ref "U2") (pin "14") (pinfunction "PB2(SS/OC1B)_14") (pintype "bidirectional"))
    )
    (net (code "93") (name "unconnected-(U2-PC0(ADC0)-Pad23)") (class "Default")
      (node (ref "U2") (pin "23") (pinfunction "PC0(ADC0)_23") (pintype "bidirectional"))
    )
    (net (code "94") (name "unconnected-(U2-PC1(ADC1)-Pad24)") (class "Default")
      (node (ref "U2") (pin "24") (pinfunction "PC1(ADC1)_24") (pintype "bidirectional"))
    )
    (net (code "95") (name "unconnected-(U2-PC2(ADC2)-Pad25)") (class "Default")
      (node (ref "U2") (pin "25") (pinfunction "PC2(ADC2)_25") (pintype "bidirectional"))
    )
    (net (code "96") (name "unconnected-(U2-PC3(ADC3)-Pad26)") (class "Default")
      (node (ref "U2") (pin "26") (pinfunction "PC3(ADC3)_26") (pintype "bidirectional"))
    )
    (net (code "97") (name "unconnected-(U2-PD4(XCK{slash}T0)-Pad2)") (class "Default")
      (node (ref "U2") (pin "2") (pinfunction "PD4(XCK/T0)_2") (pintype "bidirectional"))
    )
    (net (code "98") (name "unconnected-(U2-PD5(T1)-Pad9)") (class "Default")
      (node (ref "U2") (pin "9") (pinfunction "PD5(T1)_9") (pintype "bidirectional"))
    )
    (net (code "99") (name "unconnected-(U2-PD6(AIN0)-Pad10)") (class "Default")
      (node (ref "U2") (pin "10") (pinfunction "PD6(AIN0)_10") (pintype "bidirectional"))
    )
    (net (code "100") (name "unconnected-(U2-PD7(AIN1)-Pad11)") (class "Default")
      (node (ref "U2") (pin "11") (pinfunction "PD7(AIN1)_11") (pintype "bidirectional"))
    )
  )
)
